# E17-PDU-POWER.net
KiCad netlist of a schematic drawn in Altium Designer
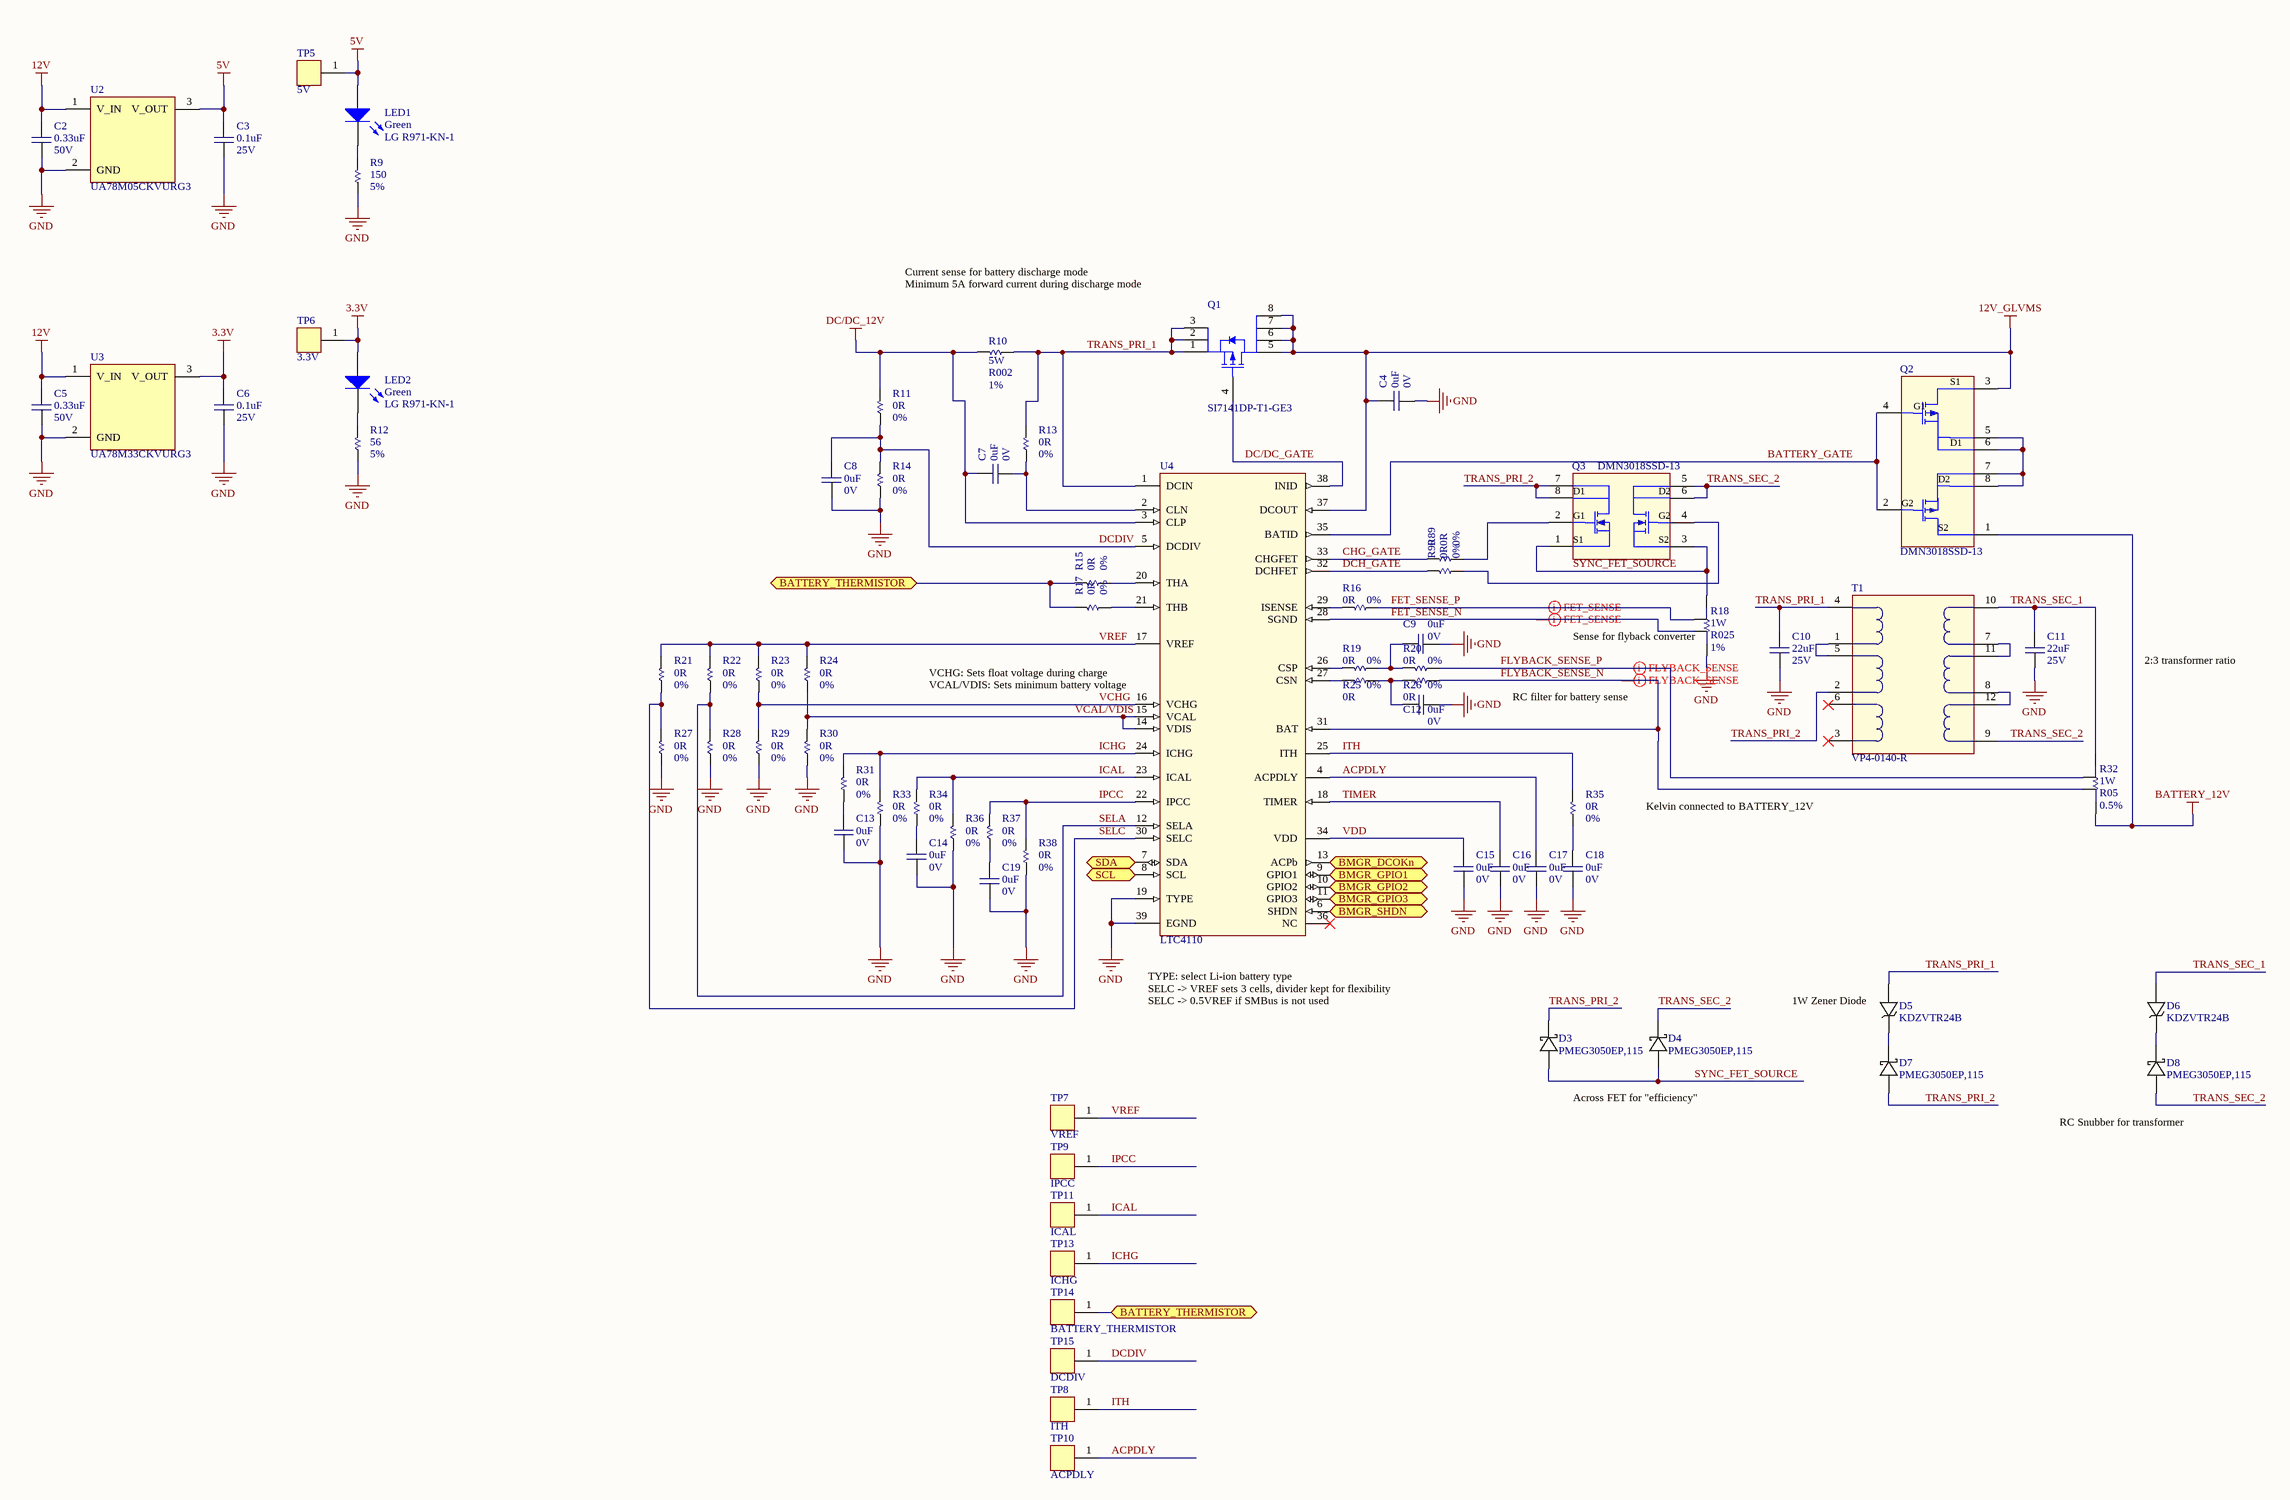
[diagram p0: E17-PDU-POWER.SchDoc]

(export (version "E")
  (design (tool "Eeschema 10.0.6"))
  (components
    (comp (ref "C2")
      (value "0.33uF")
      (footprint "C0805")
      (description "Generic 0805 Capacitor")
      (fields
        (field (name "TOLERANCE") "10%")
        (field (name "VOLTAGE") "50V")
        (field (name "Comment") "C_0805_Generic")
      )
      (libsource (lib "Compiled_PDU") (part "C_0805_Generic"))
    )
    (comp (ref "C3")
      (value "0.1uF")
      (footprint "C0805")
      (description "Generic 0805 Capacitor")
      (fields
        (field (name "TOLERANCE") "10%")
        (field (name "VOLTAGE") "25V")
        (field (name "Comment") "C_0805_Generic")
      )
      (libsource (lib "Compiled_PDU") (part "C_0805_Generic"))
    )
    (comp (ref "C4")
      (value "0uF")
      (footprint "C0603")
      (description "Generic 0603 Capacitor")
      (fields
        (field (name "TOLERANCE") "0%")
        (field (name "VOLTAGE") "0V")
        (field (name "Comment") "C_0603_Generic_1")
      )
      (libsource (lib "Compiled_PDU") (part "C_0603_Generic_1"))
    )
    (comp (ref "C5")
      (value "0.33uF")
      (footprint "C0805")
      (description "Generic 0805 Capacitor")
      (fields
        (field (name "TOLERANCE") "10%")
        (field (name "VOLTAGE") "50V")
        (field (name "Comment") "C_0805_Generic")
      )
      (libsource (lib "Compiled_PDU") (part "C_0805_Generic"))
    )
    (comp (ref "C6")
      (value "0.1uF")
      (footprint "C0805")
      (description "Generic 0805 Capacitor")
      (fields
        (field (name "TOLERANCE") "10%")
        (field (name "VOLTAGE") "25V")
        (field (name "Comment") "C_0805_Generic")
      )
      (libsource (lib "Compiled_PDU") (part "C_0805_Generic"))
    )
    (comp (ref "C7")
      (value "0uF")
      (footprint "C0603")
      (description "Generic 0603 Capacitor")
      (fields
        (field (name "TOLERANCE") "0%")
        (field (name "VOLTAGE") "0V")
        (field (name "Comment") "C_0603_Generic_1")
      )
      (libsource (lib "Compiled_PDU") (part "C_0603_Generic_1"))
    )
    (comp (ref "C8")
      (value "0uF")
      (footprint "C0603")
      (description "Generic 0603 Capacitor")
      (fields
        (field (name "TOLERANCE") "0%")
        (field (name "VOLTAGE") "0V")
        (field (name "Comment") "C_0603_Generic_1")
      )
      (libsource (lib "Compiled_PDU") (part "C_0603_Generic_1"))
    )
    (comp (ref "C9")
      (value "0uF")
      (footprint "C0402")
      (description "Generic 0402 Capacitor")
      (fields
        (field (name "TOLERANCE") "0%")
        (field (name "VOLTAGE") "0V")
        (field (name "Comment") "C_0403_Generic")
      )
      (libsource (lib "Compiled_PDU") (part "C_0403_Generic"))
    )
    (comp (ref "C10")
      (value "22uF")
      (footprint "C0805")
      (description "Generic 0805 Capacitor")
      (fields
        (field (name "TOLERANCE") "20%")
        (field (name "VOLTAGE") "25V")
        (field (name "Comment") "C_0805_Generic")
      )
      (libsource (lib "Compiled_PDU") (part "C_0805_Generic"))
    )
    (comp (ref "C11")
      (value "22uF")
      (footprint "C0805")
      (description "Generic 0805 Capacitor")
      (fields
        (field (name "TOLERANCE") "20%")
        (field (name "VOLTAGE") "25V")
        (field (name "Comment") "C_0805_Generic")
      )
      (libsource (lib "Compiled_PDU") (part "C_0805_Generic"))
    )
    (comp (ref "C12")
      (value "0uF")
      (footprint "C0402")
      (description "Generic 0402 Capacitor")
      (fields
        (field (name "TOLERANCE") "0%")
        (field (name "VOLTAGE") "0V")
        (field (name "Comment") "C_0403_Generic")
      )
      (libsource (lib "Compiled_PDU") (part "C_0403_Generic"))
    )
    (comp (ref "C13")
      (value "0uF")
      (footprint "C0402")
      (description "Generic 0402 Capacitor")
      (fields
        (field (name "TOLERANCE") "0%")
        (field (name "VOLTAGE") "0V")
        (field (name "Comment") "C_0403_Generic")
      )
      (libsource (lib "Compiled_PDU") (part "C_0403_Generic"))
    )
    (comp (ref "C14")
      (value "0uF")
      (footprint "C0402")
      (description "Generic 0402 Capacitor")
      (fields
        (field (name "TOLERANCE") "0%")
        (field (name "VOLTAGE") "0V")
        (field (name "Comment") "C_0403_Generic")
      )
      (libsource (lib "Compiled_PDU") (part "C_0403_Generic"))
    )
    (comp (ref "C15")
      (value "0uF")
      (footprint "C0603")
      (description "Generic 0603 Capacitor")
      (fields
        (field (name "TOLERANCE") "0%")
        (field (name "VOLTAGE") "0V")
        (field (name "Comment") "C_0603_Generic_1")
      )
      (libsource (lib "Compiled_PDU") (part "C_0603_Generic_1"))
    )
    (comp (ref "C16")
      (value "0uF")
      (footprint "C0402")
      (description "Generic 0402 Capacitor")
      (fields
        (field (name "TOLERANCE") "0%")
        (field (name "VOLTAGE") "0V")
        (field (name "Comment") "C_0403_Generic")
      )
      (libsource (lib "Compiled_PDU") (part "C_0403_Generic"))
    )
    (comp (ref "C17")
      (value "0uF")
      (footprint "C0402")
      (description "Generic 0402 Capacitor")
      (fields
        (field (name "TOLERANCE") "0%")
        (field (name "VOLTAGE") "0V")
        (field (name "Comment") "C_0403_Generic")
      )
      (libsource (lib "Compiled_PDU") (part "C_0403_Generic"))
    )
    (comp (ref "C18")
      (value "0uF")
      (footprint "C0402")
      (description "Generic 0402 Capacitor")
      (fields
        (field (name "TOLERANCE") "0%")
        (field (name "VOLTAGE") "0V")
        (field (name "Comment") "C_0403_Generic")
      )
      (libsource (lib "Compiled_PDU") (part "C_0403_Generic"))
    )
    (comp (ref "C19")
      (value "0uF")
      (footprint "C0402")
      (description "Generic 0402 Capacitor")
      (fields
        (field (name "TOLERANCE") "0%")
        (field (name "VOLTAGE") "0V")
        (field (name "Comment") "C_0403_Generic")
      )
      (libsource (lib "Compiled_PDU") (part "C_0403_Generic"))
    )
    (comp (ref "D3")
      (value "D_PMEG3050EP,115")
      (footprint "SOD-128")
      (description "DIODE SCHOTTKY 360mV 30V 5A")
      (fields (field (name "MFG") "Nexperia") (field (name "MFG_PN") "PMEG3050EP,115"))
      (libsource (lib "Compiled_PDU") (part "D_PMEG3050EP,115"))
    )
    (comp (ref "D4")
      (value "D_PMEG3050EP,115")
      (footprint "SOD-128")
      (description "DIODE SCHOTTKY 360mV 30V 5A")
      (fields (field (name "MFG") "Nexperia") (field (name "MFG_PN") "PMEG3050EP,115"))
      (libsource (lib "Compiled_PDU") (part "D_PMEG3050EP,115"))
    )
    (comp (ref "D5")
      (value "D_ZENER")
      (footprint "Compiled_PDU:SOD-123FL")
      (description "DIODE ZENER 24V 1W PMDU")
      (fields (field (name "MFG") "Rohm Semiconductor") (field (name "MFG_PN") "KDZVTR24B"))
      (libsource (lib "Compiled_PDU") (part "D_ZENER"))
    )
    (comp (ref "D6")
      (value "D_ZENER")
      (footprint "Compiled_PDU:SOD-123FL")
      (description "DIODE ZENER 24V 1W PMDU")
      (fields (field (name "MFG") "Rohm Semiconductor") (field (name "MFG_PN") "KDZVTR24B"))
      (libsource (lib "Compiled_PDU") (part "D_ZENER"))
    )
    (comp (ref "D7")
      (value "D_PMEG3050EP,115")
      (footprint "SOD-128")
      (description "DIODE SCHOTTKY 360mV 30V 5A")
      (fields (field (name "MFG") "Nexperia") (field (name "MFG_PN") "PMEG3050EP,115"))
      (libsource (lib "Compiled_PDU") (part "D_PMEG3050EP,115"))
    )
    (comp (ref "D8")
      (value "D_PMEG3050EP,115")
      (footprint "SOD-128")
      (description "DIODE SCHOTTKY 360mV 30V 5A")
      (fields (field (name "MFG") "Nexperia") (field (name "MFG_PN") "PMEG3050EP,115"))
      (libsource (lib "Compiled_PDU") (part "D_PMEG3050EP,115"))
    )
    (comp (ref "LED1")
      (value "Green")
      (footprint "LGR971")
      (description "Green LED")
      (fields (field (name "MFG") "OSRAM Opto Semiconductors Inc.") (field (name "MFG_PN") "LG R971-KN-1"))
      (libsource (lib "Compiled_PDU") (part "LED_LGR971"))
    )
    (comp (ref "LED2")
      (value "Green")
      (footprint "LGR971")
      (description "Green LED")
      (fields (field (name "MFG") "OSRAM Opto Semiconductors Inc.") (field (name "MFG_PN") "LG R971-KN-1"))
      (libsource (lib "Compiled_PDU") (part "LED_LGR971"))
    )
    (comp (ref "Q1")
      (value "Q_SI7141DP-T1-GE3")
      (footprint "PowerPak SO-8")
      (description "P-CH 20V 60A PowerPak SO-8")
      (fields (field (name "MFG") "Vishay") (field (name "MFG_PN") "SI7141DP-T1-GE3"))
      (libsource (lib "Compiled_PDU") (part "Q_SI7141DP-T1-GE3"))
    )
    (comp (ref "Q2")
      (value "Q_DMN3018SSD-13_1")
      (footprint "8-SOIC")
      (description "2x P-ch FET 40V 6.7A")
      (fields (field (name "MFG") "ON Semiconductor") (field (name "MFG_PN") "DMN3018SSD-13"))
      (libsource (lib "Compiled_PDU") (part "Q_DMN3018SSD-13_1"))
    )
    (comp (ref "Q3")
      (value "Q_DMN3018SSD-13")
      (footprint "8-SOIC")
      (description "2x N-ch FET 40V 6.7A")
      (fields (field (name "MFG") "ON Semiconductor") (field (name "MFG_PN") "DMN3018SSD-13"))
      (libsource (lib "Compiled_PDU") (part "Q_DMN3018SSD-13"))
    )
    (comp (ref "R9")
      (value "150")
      (footprint "R0805")
      (description "Generic 0805 Resistor")
      (fields
        (field (name "POWER") "1/8W")
        (field (name "TOLERANCE") "5%")
        (field (name "Comment") "R_0805_Generic")
      )
      (libsource (lib "Compiled_PDU") (part "R_0805_Generic"))
    )
    (comp (ref "R10")
      (value "R002")
      (footprint "R2526")
      (description "RES CURRENT SENSE R002 1% 5W")
      (fields
        (field (name "MFG") "Panasonic")
        (field (name "POWER") "5W")
        (field (name "TOLERANCE") "1%")
        (field (name "Comment") "R_ERJ-MS6SF2M0U")
      )
      (libsource (lib "Compiled_PDU") (part "R_ERJ-MS6SF2M0U"))
    )
    (comp (ref "R11")
      (value "0R")
      (footprint "R0603")
      (description "Generic 0603 Resistor")
      (fields
        (field (name "POWER") "0W")
        (field (name "TOLERANCE") "0%")
        (field (name "Comment") "R_0603_Generic")
      )
      (libsource (lib "Compiled_PDU") (part "R_0603_Generic"))
    )
    (comp (ref "R12")
      (value "56")
      (footprint "R0805")
      (description "Generic 0805 Resistor")
      (fields
        (field (name "POWER") "1/8W")
        (field (name "TOLERANCE") "5%")
        (field (name "Comment") "R_0805_Generic")
      )
      (libsource (lib "Compiled_PDU") (part "R_0805_Generic"))
    )
    (comp (ref "R13")
      (value "0R")
      (footprint "R0603")
      (description "Generic 0603 Resistor")
      (fields
        (field (name "POWER") "0W")
        (field (name "TOLERANCE") "0%")
        (field (name "Comment") "R_0603_Generic")
      )
      (libsource (lib "Compiled_PDU") (part "R_0603_Generic"))
    )
    (comp (ref "R14")
      (value "0R")
      (footprint "R0603")
      (description "Generic 0603 Resistor")
      (fields
        (field (name "POWER") "0W")
        (field (name "TOLERANCE") "0%")
        (field (name "Comment") "R_0603_Generic")
      )
      (libsource (lib "Compiled_PDU") (part "R_0603_Generic"))
    )
    (comp (ref "R15")
      (value "0R")
      (footprint "R0603")
      (description "Generic 0603 Resistor")
      (fields
        (field (name "POWER") "0W")
        (field (name "TOLERANCE") "0%")
        (field (name "Comment") "R_0603_Generic")
      )
      (libsource (lib "Compiled_PDU") (part "R_0603_Generic"))
    )
    (comp (ref "R16")
      (value "0R")
      (footprint "R0402")
      (description "Generic 0402 Resistor")
      (fields
        (field (name "POWER") "0W")
        (field (name "TOLERANCE") "0%")
        (field (name "Comment") "R_0402_Generic")
      )
      (libsource (lib "Compiled_PDU") (part "R_0402_Generic"))
    )
    (comp (ref "R17")
      (value "0R")
      (footprint "R0603")
      (description "Generic 0603 Resistor")
      (fields
        (field (name "POWER") "0W")
        (field (name "TOLERANCE") "0%")
        (field (name "Comment") "R_0603_Generic")
      )
      (libsource (lib "Compiled_PDU") (part "R_0603_Generic"))
    )
    (comp (ref "R18")
      (value "R025")
      (footprint "R2512")
      (description "RES CURRENT SENSE R025 1% 1W")
      (fields
        (field (name "MFG") "Ohmite")
        (field (name "POWER") "1W")
        (field (name "TOLERANCE") "1%")
        (field (name "Comment") "R_LVK24R025FER")
      )
      (libsource (lib "Compiled_PDU") (part "R_LVK24R025FER"))
    )
    (comp (ref "R19")
      (value "0R")
      (footprint "R0402")
      (description "Generic 0402 Resistor")
      (fields
        (field (name "POWER") "0W")
        (field (name "TOLERANCE") "0%")
        (field (name "Comment") "R_0402_Generic")
      )
      (libsource (lib "Compiled_PDU") (part "R_0402_Generic"))
    )
    (comp (ref "R20")
      (value "0R")
      (footprint "R0402")
      (description "Generic 0402 Resistor")
      (fields
        (field (name "POWER") "0W")
        (field (name "TOLERANCE") "0%")
        (field (name "Comment") "R_0402_Generic")
      )
      (libsource (lib "Compiled_PDU") (part "R_0402_Generic"))
    )
    (comp (ref "R21")
      (value "0R")
      (footprint "R0402")
      (description "Generic 0402 Resistor")
      (fields
        (field (name "POWER") "0W")
        (field (name "TOLERANCE") "0%")
        (field (name "Comment") "R_0402_Generic")
      )
      (libsource (lib "Compiled_PDU") (part "R_0402_Generic"))
    )
    (comp (ref "R22")
      (value "0R")
      (footprint "R0402")
      (description "Generic 0402 Resistor")
      (fields
        (field (name "POWER") "0W")
        (field (name "TOLERANCE") "0%")
        (field (name "Comment") "R_0402_Generic")
      )
      (libsource (lib "Compiled_PDU") (part "R_0402_Generic"))
    )
    (comp (ref "R23")
      (value "0R")
      (footprint "R0402")
      (description "Generic 0402 Resistor")
      (fields
        (field (name "POWER") "0W")
        (field (name "TOLERANCE") "0%")
        (field (name "Comment") "R_0402_Generic")
      )
      (libsource (lib "Compiled_PDU") (part "R_0402_Generic"))
    )
    (comp (ref "R24")
      (value "0R")
      (footprint "R0402")
      (description "Generic 0402 Resistor")
      (fields
        (field (name "POWER") "0W")
        (field (name "TOLERANCE") "0%")
        (field (name "Comment") "R_0402_Generic")
      )
      (libsource (lib "Compiled_PDU") (part "R_0402_Generic"))
    )
    (comp (ref "R25")
      (value "0R")
      (footprint "R0402")
      (description "Generic 0402 Resistor")
      (fields
        (field (name "POWER") "0W")
        (field (name "TOLERANCE") "0%")
        (field (name "Comment") "R_0402_Generic")
      )
      (libsource (lib "Compiled_PDU") (part "R_0402_Generic"))
    )
    (comp (ref "R26")
      (value "0R")
      (footprint "R0402")
      (description "Generic 0402 Resistor")
      (fields
        (field (name "POWER") "0W")
        (field (name "TOLERANCE") "0%")
        (field (name "Comment") "R_0402_Generic")
      )
      (libsource (lib "Compiled_PDU") (part "R_0402_Generic"))
    )
    (comp (ref "R27")
      (value "0R")
      (footprint "R0402")
      (description "Generic 0402 Resistor")
      (fields
        (field (name "POWER") "0W")
        (field (name "TOLERANCE") "0%")
        (field (name "Comment") "R_0402_Generic")
      )
      (libsource (lib "Compiled_PDU") (part "R_0402_Generic"))
    )
    (comp (ref "R28")
      (value "0R")
      (footprint "R0402")
      (description "Generic 0402 Resistor")
      (fields
        (field (name "POWER") "0W")
        (field (name "TOLERANCE") "0%")
        (field (name "Comment") "R_0402_Generic")
      )
      (libsource (lib "Compiled_PDU") (part "R_0402_Generic"))
    )
    (comp (ref "R29")
      (value "0R")
      (footprint "R0402")
      (description "Generic 0402 Resistor")
      (fields
        (field (name "POWER") "0W")
        (field (name "TOLERANCE") "0%")
        (field (name "Comment") "R_0402_Generic")
      )
      (libsource (lib "Compiled_PDU") (part "R_0402_Generic"))
    )
    (comp (ref "R30")
      (value "0R")
      (footprint "R0402")
      (description "Generic 0402 Resistor")
      (fields
        (field (name "POWER") "0W")
        (field (name "TOLERANCE") "0%")
        (field (name "Comment") "R_0402_Generic")
      )
      (libsource (lib "Compiled_PDU") (part "R_0402_Generic"))
    )
    (comp (ref "R31")
      (value "0R")
      (footprint "R0402")
      (description "Generic 0402 Resistor")
      (fields
        (field (name "POWER") "0W")
        (field (name "TOLERANCE") "0%")
        (field (name "Comment") "R_0402_Generic")
      )
      (libsource (lib "Compiled_PDU") (part "R_0402_Generic"))
    )
    (comp (ref "R32")
      (value "R05")
      (footprint "R2512")
      (description "RES CURRENT SENSE R05 0.5% 1W")
      (fields
        (field (name "MFG") "Ohmite")
        (field (name "POWER") "1W")
        (field (name "TOLERANCE") "0.5%")
        (field (name "Comment") "R_LVK24R050DER")
      )
      (libsource (lib "Compiled_PDU") (part "R_LVK24R050DER"))
    )
    (comp (ref "R33")
      (value "0R")
      (footprint "R0402")
      (description "Generic 0402 Resistor")
      (fields
        (field (name "POWER") "0W")
        (field (name "TOLERANCE") "0%")
        (field (name "Comment") "R_0402_Generic")
      )
      (libsource (lib "Compiled_PDU") (part "R_0402_Generic"))
    )
    (comp (ref "R34")
      (value "0R")
      (footprint "R0402")
      (description "Generic 0402 Resistor")
      (fields
        (field (name "POWER") "0W")
        (field (name "TOLERANCE") "0%")
        (field (name "Comment") "R_0402_Generic")
      )
      (libsource (lib "Compiled_PDU") (part "R_0402_Generic"))
    )
    (comp (ref "R35")
      (value "0R")
      (footprint "R0402")
      (description "Generic 0402 Resistor")
      (fields
        (field (name "POWER") "0W")
        (field (name "TOLERANCE") "0%")
        (field (name "Comment") "R_0402_Generic")
      )
      (libsource (lib "Compiled_PDU") (part "R_0402_Generic"))
    )
    (comp (ref "R36")
      (value "0R")
      (footprint "R0402")
      (description "Generic 0402 Resistor")
      (fields
        (field (name "POWER") "0W")
        (field (name "TOLERANCE") "0%")
        (field (name "Comment") "R_0402_Generic")
      )
      (libsource (lib "Compiled_PDU") (part "R_0402_Generic"))
    )
    (comp (ref "R37")
      (value "0R")
      (footprint "R0402")
      (description "Generic 0402 Resistor")
      (fields
        (field (name "POWER") "0W")
        (field (name "TOLERANCE") "0%")
        (field (name "Comment") "R_0402_Generic")
      )
      (libsource (lib "Compiled_PDU") (part "R_0402_Generic"))
    )
    (comp (ref "R38")
      (value "0R")
      (footprint "R0402")
      (description "Generic 0402 Resistor")
      (fields
        (field (name "POWER") "0W")
        (field (name "TOLERANCE") "0%")
        (field (name "Comment") "R_0402_Generic")
      )
      (libsource (lib "Compiled_PDU") (part "R_0402_Generic"))
    )
    (comp (ref "R89")
      (value "0R")
      (footprint "R0603")
      (description "Generic 0603 Resistor")
      (fields
        (field (name "POWER") "0W")
        (field (name "TOLERANCE") "0%")
        (field (name "Comment") "R_0603_Generic")
      )
      (libsource (lib "Compiled_PDU") (part "R_0603_Generic"))
    )
    (comp (ref "R90")
      (value "0R")
      (footprint "R0603")
      (description "Generic 0603 Resistor")
      (fields
        (field (name "POWER") "0W")
        (field (name "TOLERANCE") "0%")
        (field (name "Comment") "R_0603_Generic")
      )
      (libsource (lib "Compiled_PDU") (part "R_0603_Generic"))
    )
    (comp (ref "T1")
      (value "T_VP4-0140-R")
      (footprint "T_VP4-0140-R")
      (description "Transformer 6 coil 11.3uH")
      (fields (field (name "MFG") "Eaton") (field (name "MFG_PN") "VP4-0140-R"))
      (libsource (lib "Compiled_PDU") (part "T_VP4-0140-R"))
    )
    (comp (ref "TP5")
      (value "5V")
      (footprint "TEST POINT")
      (description "Test Point")
      (libsource (lib "Compiled_PDU") (part "Test Point"))
    )
    (comp (ref "TP6")
      (value "3.3V")
      (footprint "TEST POINT")
      (description "Test Point")
      (libsource (lib "Compiled_PDU") (part "Test Point"))
    )
    (comp (ref "TP7")
      (value "VREF")
      (footprint "TEST POINT")
      (description "Test Point")
      (libsource (lib "Compiled_PDU") (part "Test Point"))
    )
    (comp (ref "TP8")
      (value "ITH")
      (footprint "TEST POINT")
      (description "Test Point")
      (libsource (lib "Compiled_PDU") (part "Test Point"))
    )
    (comp (ref "TP9")
      (value "IPCC")
      (footprint "TEST POINT")
      (description "Test Point")
      (libsource (lib "Compiled_PDU") (part "Test Point"))
    )
    (comp (ref "TP10")
      (value "ACPDLY")
      (footprint "TEST POINT")
      (description "Test Point")
      (libsource (lib "Compiled_PDU") (part "Test Point"))
    )
    (comp (ref "TP11")
      (value "ICAL")
      (footprint "TEST POINT")
      (description "Test Point")
      (libsource (lib "Compiled_PDU") (part "Test Point"))
    )
    (comp (ref "TP13")
      (value "ICHG")
      (footprint "TEST POINT")
      (description "Test Point")
      (libsource (lib "Compiled_PDU") (part "Test Point"))
    )
    (comp (ref "TP14")
      (value "BATTERY_THERMISTOR")
      (footprint "TEST POINT")
      (description "Test Point")
      (libsource (lib "Compiled_PDU") (part "Test Point"))
    )
    (comp (ref "TP15")
      (value "DCDIV")
      (footprint "TEST POINT")
      (description "Test Point")
      (libsource (lib "Compiled_PDU") (part "Test Point"))
    )
    (comp (ref "U2")
      (value "U_UA78M05CKVURG3")
      (footprint "TO-252-3")
      (description "5V 500mA Linear Regulator")
      (fields (field (name "MFG") "TI") (field (name "MFG_PN") "UA78M05CKVURG3"))
      (libsource (lib "Compiled_PDU") (part "U_UA78M05CKVURG3"))
    )
    (comp (ref "U3")
      (value "U_UA78M33CKVURG3")
      (footprint "TO-252-3")
      (description "3.3V 500mA Linear Regulator")
      (fields (field (name "MFG") "TI") (field (name "MFG_PN") "UA78M33CKVURG3"))
      (libsource (lib "Compiled_PDU") (part "U_UA78M33CKVURG3"))
    )
    (comp (ref "U4")
      (value "U_LTC4110")
      (footprint "U_LTC4110")
      (description "IC Battery Backup Manager")
      (fields (field (name "MFG") "Linear Technology") (field (name "MFG_PN") "LTC4110"))
      (libsource (lib "Compiled_PDU") (part "U_LTC4110"))
    )
  )
  (nets
    (net (code "1") (name "/ACPDLY") (class "Default")
      (node (ref "C17") (pin "1") (pinfunction "EGND_1") (pintype "passive"))
      (node (ref "TP10") (pin "1") (pintype "passive"))
      (node (ref "U4") (pin "4") (pinfunction "ACPDLY_4") (pintype "passive"))
    )
    (net (code "2") (name "/BATTERY_GATE") (class "Default")
      (node (ref "Q2") (pin "2") (pintype "passive"))
      (node (ref "Q2") (pin "4") (pinfunction "4_4") (pintype "passive"))
      (node (ref "U4") (pin "35") (pinfunction "BATID_35") (pintype "output"))
    )
    (net (code "3") (name "/BATTERY_THERMISTOR") (class "Default")
      (node (ref "R15") (pin "1") (pinfunction "1_1") (pintype "passive"))
      (node (ref "R17") (pin "1") (pinfunction "1_1") (pintype "passive"))
      (node (ref "TP14") (pin "1") (pintype "passive"))
    )
    (net (code "4") (name "/BMGR_DCOKn") (class "Default")
      (node (ref "U4") (pin "13") (pinfunction "ACPb_13") (pintype "output"))
    )
    (net (code "5") (name "/BMGR_GPIO1") (class "Default")
      (node (ref "U4") (pin "9") (pinfunction "GPIO1_9") (pintype "bidirectional"))
    )
    (net (code "6") (name "/BMGR_GPIO2") (class "Default")
      (node (ref "U4") (pin "10") (pinfunction "GPIO2_10") (pintype "bidirectional"))
    )
    (net (code "7") (name "/BMGR_GPIO3") (class "Default")
      (node (ref "U4") (pin "11") (pinfunction "GPIO3_11") (pintype "bidirectional"))
    )
    (net (code "8") (name "/BMGR_SHDN") (class "Default")
      (node (ref "U4") (pin "6") (pinfunction "SHDN_6") (pintype "input"))
    )
    (net (code "9") (name "/CHG_GATE") (class "Default")
      (node (ref "R89") (pin "1") (pinfunction "1_1") (pintype "passive"))
      (node (ref "U4") (pin "33") (pinfunction "CHGFET_33") (pintype "output"))
    )
    (net (code "10") (name "/DCDIV") (class "Default")
      (node (ref "C8") (pin "1") (pinfunction "EGND_1") (pintype "passive"))
      (node (ref "R11") (pin "2") (pinfunction "2_2") (pintype "passive"))
      (node (ref "R14") (pin "1") (pinfunction "1_1") (pintype "passive"))
      (node (ref "TP15") (pin "1") (pintype "passive"))
      (node (ref "U4") (pin "5") (pinfunction "DCDIV_5") (pintype "input"))
    )
    (net (code "11") (name "/DCH_GATE") (class "Default")
      (node (ref "R90") (pin "1") (pinfunction "1_1") (pintype "passive"))
      (node (ref "U4") (pin "32") (pinfunction "DCHFET_32") (pintype "output"))
    )
    (net (code "12") (name "/DC{slash}DC_GATE") (class "Default")
      (node (ref "Q1") (pin "4") (pinfunction "G_4") (pintype "passive"))
      (node (ref "U4") (pin "38") (pinfunction "INID_38") (pintype "output"))
    )
    (net (code "13") (name "/FET_SENSE_N") (class "Default")
      (node (ref "R18") (pin "3") (pinfunction "3_3") (pintype "passive"))
      (node (ref "U4") (pin "28") (pinfunction "SGND_28") (pintype "input"))
    )
    (net (code "14") (name "/FET_SENSE_P") (class "Default")
      (node (ref "R16") (pin "2") (pinfunction "2_2") (pintype "passive"))
      (node (ref "R18") (pin "4") (pinfunction "4_4") (pintype "passive"))
    )
    (net (code "15") (name "/FLYBACK_SENSE_N") (class "Default")
      (node (ref "R26") (pin "2") (pinfunction "2_2") (pintype "passive"))
      (node (ref "R32") (pin "3") (pinfunction "3_3") (pintype "passive"))
      (node (ref "U4") (pin "31") (pinfunction "BAT_31") (pintype "input"))
    )
    (net (code "16") (name "/FLYBACK_SENSE_P") (class "Default")
      (node (ref "R20") (pin "2") (pinfunction "2_2") (pintype "passive"))
      (node (ref "R32") (pin "4") (pinfunction "4_4") (pintype "passive"))
    )
    (net (code "17") (name "/ICAL") (class "Default")
      (node (ref "R34") (pin "1") (pinfunction "1_1") (pintype "passive"))
      (node (ref "R36") (pin "1") (pinfunction "1_1") (pintype "passive"))
      (node (ref "TP11") (pin "1") (pintype "passive"))
      (node (ref "U4") (pin "23") (pinfunction "ICAL_23") (pintype "input"))
    )
    (net (code "18") (name "/ICHG") (class "Default")
      (node (ref "R31") (pin "1") (pinfunction "1_1") (pintype "passive"))
      (node (ref "R33") (pin "1") (pinfunction "1_1") (pintype "passive"))
      (node (ref "TP13") (pin "1") (pintype "passive"))
      (node (ref "U4") (pin "24") (pinfunction "ICHG_24") (pintype "input"))
    )
    (net (code "19") (name "/IPCC") (class "Default")
      (node (ref "R37") (pin "1") (pinfunction "1_1") (pintype "passive"))
      (node (ref "R38") (pin "1") (pinfunction "1_1") (pintype "passive"))
      (node (ref "TP9") (pin "1") (pintype "passive"))
      (node (ref "U4") (pin "22") (pinfunction "IPCC_22") (pintype "input"))
    )
    (net (code "20") (name "/ITH") (class "Default")
      (node (ref "R35") (pin "1") (pinfunction "1_1") (pintype "passive"))
      (node (ref "TP8") (pin "1") (pintype "passive"))
      (node (ref "U4") (pin "25") (pinfunction "ITH_25") (pintype "passive"))
    )
    (net (code "21") (name "/SCL") (class "Default")
      (node (ref "U4") (pin "8") (pinfunction "SCL_8") (pintype "input"))
    )
    (net (code "22") (name "/SDA") (class "Default")
      (node (ref "U4") (pin "7") (pinfunction "SDA_7") (pintype "bidirectional"))
    )
    (net (code "23") (name "/SELA") (class "Default")
      (node (ref "R22") (pin "2") (pinfunction "2_2") (pintype "passive"))
      (node (ref "R28") (pin "1") (pinfunction "1_1") (pintype "passive"))
      (node (ref "U4") (pin "12") (pinfunction "SELA_12") (pintype "input"))
    )
    (net (code "24") (name "/SELC") (class "Default")
      (node (ref "R21") (pin "2") (pinfunction "2_2") (pintype "passive"))
      (node (ref "R27") (pin "1") (pinfunction "1_1") (pintype "passive"))
      (node (ref "U4") (pin "30") (pinfunction "SELC_30") (pintype "input"))
    )
    (net (code "25") (name "/SYNC_FET_SOURCE") (class "Default")
      (node (ref "D3") (pin "1") (pintype "passive"))
      (node (ref "D4") (pin "1") (pintype "passive"))
      (node (ref "Q3") (pin "1") (pintype "passive"))
      (node (ref "Q3") (pin "3") (pinfunction "3_3") (pintype "passive"))
      (node (ref "R18") (pin "2") (pinfunction "2_2") (pintype "passive"))
    )
    (net (code "26") (name "/TIMER") (class "Default")
      (node (ref "C16") (pin "1") (pinfunction "EGND_1") (pintype "passive"))
      (node (ref "U4") (pin "18") (pinfunction "TIMER_18") (pintype "input"))
    )
    (net (code "27") (name "/TRANS_PRI_1") (class "Default")
      (node (ref "C10") (pin "1") (pinfunction "EGND_1") (pintype "passive"))
      (node (ref "D5") (pin "1") (pintype "passive"))
      (node (ref "Q1") (pin "1") (pintype "passive"))
      (node (ref "Q1") (pin "2") (pinfunction "5_2") (pintype "passive"))
      (node (ref "Q1") (pin "3") (pinfunction "6_3") (pintype "passive"))
      (node (ref "R10") (pin "2") (pinfunction "2_2") (pintype "passive"))
      (node (ref "R13") (pin "1") (pinfunction "1_1") (pintype "passive"))
      (node (ref "T1") (pin "4") (pinfunction "4_4") (pintype "passive"))
      (node (ref "U4") (pin "1") (pinfunction "DCIN_1") (pintype "power_in"))
    )
    (net (code "28") (name "/TRANS_PRI_2") (class "Default")
      (node (ref "D3") (pin "2") (pintype "passive"))
      (node (ref "D7") (pin "1") (pintype "passive"))
      (node (ref "Q3") (pin "7") (pinfunction "7_7") (pintype "passive"))
      (node (ref "Q3") (pin "8") (pinfunction "8_8") (pintype "passive"))
      (node (ref "T1") (pin "2") (pinfunction "2_2") (pintype "passive"))
    )
    (net (code "29") (name "/TRANS_SEC_1") (class "Default")
      (node (ref "C11") (pin "1") (pinfunction "EGND_1") (pintype "passive"))
      (node (ref "D6") (pin "1") (pintype "passive"))
      (node (ref "R32") (pin "2") (pinfunction "2_2") (pintype "passive"))
      (node (ref "T1") (pin "10") (pinfunction "10_10") (pintype "passive"))
    )
    (net (code "30") (name "/TRANS_SEC_2") (class "Default")
      (node (ref "D4") (pin "2") (pintype "passive"))
      (node (ref "D8") (pin "1") (pintype "passive"))
      (node (ref "Q3") (pin "5") (pinfunction "5_5") (pintype "passive"))
      (node (ref "Q3") (pin "6") (pinfunction "6_6") (pintype "passive"))
      (node (ref "T1") (pin "9") (pinfunction "9_9") (pintype "passive"))
    )
    (net (code "31") (name "/VCAL{slash}VDIS") (class "Default")
      (node (ref "R24") (pin "2") (pinfunction "2_2") (pintype "passive"))
      (node (ref "R30") (pin "1") (pinfunction "1_1") (pintype "passive"))
      (node (ref "U4") (pin "14") (pinfunction "VDIS_14") (pintype "input"))
      (node (ref "U4") (pin "15") (pinfunction "VCAL_15") (pintype "input"))
    )
    (net (code "32") (name "/VCHG") (class "Default")
      (node (ref "R23") (pin "2") (pinfunction "2_2") (pintype "passive"))
      (node (ref "R29") (pin "1") (pinfunction "1_1") (pintype "passive"))
      (node (ref "U4") (pin "16") (pinfunction "VCHG_16") (pintype "input"))
    )
    (net (code "33") (name "/VDD") (class "Default")
      (node (ref "C15") (pin "1") (pinfunction "EGND_1") (pintype "passive"))
      (node (ref "U4") (pin "34") (pinfunction "VDD_34") (pintype "power_in"))
    )
    (net (code "34") (name "/VREF") (class "Default")
      (node (ref "R21") (pin "1") (pinfunction "1_1") (pintype "passive"))
      (node (ref "R22") (pin "1") (pinfunction "1_1") (pintype "passive"))
      (node (ref "R23") (pin "1") (pinfunction "1_1") (pintype "passive"))
      (node (ref "R24") (pin "1") (pinfunction "1_1") (pintype "passive"))
      (node (ref "TP7") (pin "1") (pintype "passive"))
      (node (ref "U4") (pin "17") (pinfunction "VREF_17") (pintype "power_in"))
    )
    (net (code "35") (name "3.3V") (class "Default")
      (node (ref "C6") (pin "1") (pinfunction "EGND_1") (pintype "passive"))
      (node (ref "LED2") (pin "1") (pinfunction "A_1") (pintype "passive"))
      (node (ref "TP6") (pin "1") (pintype "passive"))
      (node (ref "U3") (pin "3") (pinfunction "V_OUT_3") (pintype "power_in"))
    )
    (net (code "36") (name "5V") (class "Default")
      (node (ref "C3") (pin "1") (pinfunction "EGND_1") (pintype "passive"))
      (node (ref "LED1") (pin "1") (pinfunction "A_1") (pintype "passive"))
      (node (ref "TP5") (pin "1") (pintype "passive"))
      (node (ref "U2") (pin "3") (pinfunction "V_OUT_3") (pintype "power_in"))
    )
    (net (code "37") (name "12V") (class "Default")
      (node (ref "C2") (pin "1") (pinfunction "EGND_1") (pintype "passive"))
      (node (ref "C5") (pin "1") (pinfunction "EGND_1") (pintype "passive"))
      (node (ref "U2") (pin "1") (pinfunction "V_IN_1") (pintype "power_in"))
      (node (ref "U3") (pin "1") (pinfunction "V_IN_1") (pintype "passive"))
    )
    (net (code "38") (name "12V_GLVMS") (class "Default")
      (node (ref "C4") (pin "1") (pinfunction "EGND_1") (pintype "passive"))
      (node (ref "Q1") (pin "5") (pinfunction "5_5") (pintype "passive"))
      (node (ref "Q1") (pin "6") (pinfunction "6_6") (pintype "passive"))
      (node (ref "Q1") (pin "7") (pinfunction "7_7") (pintype "passive"))
      (node (ref "Q1") (pin "8") (pinfunction "8_8") (pintype "passive"))
      (node (ref "Q2") (pin "3") (pinfunction "3_3") (pintype "passive"))
      (node (ref "U4") (pin "37") (pinfunction "DCOUT_37") (pintype "input"))
    )
    (net (code "39") (name "BATTERY_12V") (class "Default")
      (node (ref "Q2") (pin "1") (pintype "passive"))
      (node (ref "R32") (pin "1") (pinfunction "1_1") (pintype "passive"))
    )
    (net (code "40") (name "DC{slash}DC_12V") (class "Default")
      (node (ref "C7") (pin "1") (pinfunction "EGND_1") (pintype "passive"))
      (node (ref "R10") (pin "1") (pinfunction "1_1") (pintype "passive"))
      (node (ref "R11") (pin "1") (pinfunction "1_1") (pintype "passive"))
      (node (ref "U4") (pin "3") (pinfunction "CLP_3") (pintype "input"))
    )
    (net (code "41") (name "GND") (class "Default")
      (node (ref "C10") (pin "2") (pinfunction "2_2") (pintype "passive"))
      (node (ref "C11") (pin "2") (pinfunction "2_2") (pintype "passive"))
      (node (ref "C12") (pin "1") (pinfunction "EGND_1") (pintype "passive"))
      (node (ref "C13") (pin "2") (pinfunction "2_2") (pintype "passive"))
      (node (ref "C14") (pin "2") (pinfunction "2_2") (pintype "passive"))
      (node (ref "C15") (pin "2") (pinfunction "2_2") (pintype "passive"))
      (node (ref "C16") (pin "2") (pinfunction "2_2") (pintype "passive"))
      (node (ref "C17") (pin "2") (pinfunction "2_2") (pintype "passive"))
      (node (ref "C18") (pin "2") (pinfunction "2_2") (pintype "passive"))
      (node (ref "C19") (pin "2") (pinfunction "2_2") (pintype "passive"))
      (node (ref "C2") (pin "2") (pinfunction "2_2") (pintype "passive"))
      (node (ref "C3") (pin "2") (pinfunction "2_2") (pintype "passive"))
      (node (ref "C4") (pin "2") (pinfunction "2_2") (pintype "passive"))
      (node (ref "C5") (pin "2") (pinfunction "2_2") (pintype "passive"))
      (node (ref "C6") (pin "2") (pinfunction "2_2") (pintype "passive"))
      (node (ref "C8") (pin "2") (pinfunction "2_2") (pintype "passive"))
      (node (ref "C9") (pin "2") (pinfunction "2_2") (pintype "passive"))
      (node (ref "R12") (pin "2") (pinfunction "2_2") (pintype "passive"))
      (node (ref "R14") (pin "2") (pinfunction "2_2") (pintype "passive"))
      (node (ref "R18") (pin "1") (pinfunction "1_1") (pintype "passive"))
      (node (ref "R27") (pin "2") (pinfunction "2_2") (pintype "passive"))
      (node (ref "R28") (pin "2") (pinfunction "2_2") (pintype "passive"))
      (node (ref "R29") (pin "2") (pinfunction "2_2") (pintype "passive"))
      (node (ref "R30") (pin "2") (pinfunction "2_2") (pintype "passive"))
      (node (ref "R33") (pin "2") (pinfunction "2_2") (pintype "passive"))
      (node (ref "R36") (pin "2") (pinfunction "2_2") (pintype "passive"))
      (node (ref "R38") (pin "2") (pinfunction "2_2") (pintype "passive"))
      (node (ref "R9") (pin "2") (pinfunction "2_2") (pintype "passive"))
      (node (ref "U2") (pin "2") (pinfunction "GND_2") (pintype "power_in"))
      (node (ref "U3") (pin "2") (pinfunction "GND_2") (pintype "power_in"))
      (node (ref "U4") (pin "19") (pinfunction "TYPE_19") (pintype "input"))
      (node (ref "U4") (pin "39") (pinfunction "EGND_39") (pintype "power_in"))
    )
    (net (code "42") (name "Net-(C9-EGND)") (class "Default")
      (node (ref "C9") (pin "1") (pinfunction "EGND_1") (pintype "passive"))
      (node (ref "R19") (pin "2") (pinfunction "2_2") (pintype "passive"))
      (node (ref "R20") (pin "1") (pinfunction "1_1") (pintype "passive"))
    )
    (net (code "43") (name "Net-(C12-Pad2)") (class "Default")
      (node (ref "C12") (pin "2") (pinfunction "2_2") (pintype "passive"))
      (node (ref "R25") (pin "2") (pinfunction "2_2") (pintype "passive"))
      (node (ref "R26") (pin "1") (pinfunction "1_1") (pintype "passive"))
    )
    (net (code "44") (name "Net-(C13-EGND)") (class "Default")
      (node (ref "C13") (pin "1") (pinfunction "EGND_1") (pintype "passive"))
      (node (ref "R31") (pin "2") (pinfunction "2_2") (pintype "passive"))
    )
    (net (code "45") (name "Net-(C14-EGND)") (class "Default")
      (node (ref "C14") (pin "1") (pinfunction "EGND_1") (pintype "passive"))
      (node (ref "R34") (pin "2") (pinfunction "2_2") (pintype "passive"))
    )
    (net (code "46") (name "Net-(C18-EGND)") (class "Default")
      (node (ref "C18") (pin "1") (pinfunction "EGND_1") (pintype "passive"))
      (node (ref "R35") (pin "2") (pinfunction "2_2") (pintype "passive"))
    )
    (net (code "47") (name "Net-(C19-EGND)") (class "Default")
      (node (ref "C19") (pin "1") (pinfunction "EGND_1") (pintype "passive"))
      (node (ref "R37") (pin "2") (pinfunction "2_2") (pintype "passive"))
    )
    (net (code "48") (name "Net-(D5-Pad2)") (class "Default")
      (node (ref "D5") (pin "2") (pintype "passive"))
      (node (ref "D7") (pin "2") (pintype "passive"))
    )
    (net (code "49") (name "Net-(D6-Pad2)") (class "Default")
      (node (ref "D6") (pin "2") (pintype "passive"))
      (node (ref "D8") (pin "2") (pintype "passive"))
    )
    (net (code "50") (name "Net-(LED1-K)") (class "Default")
      (node (ref "LED1") (pin "2") (pinfunction "K_2") (pintype "passive"))
      (node (ref "R9") (pin "1") (pinfunction "1_1") (pintype "passive"))
    )
    (net (code "51") (name "Net-(LED2-K)") (class "Default")
      (node (ref "LED2") (pin "2") (pinfunction "K_2") (pintype "passive"))
      (node (ref "R12") (pin "1") (pinfunction "1_1") (pintype "passive"))
    )
    (net (code "52") (name "Net-(Q2-Pad5)") (class "Default")
      (node (ref "Q2") (pin "5") (pinfunction "5_5") (pintype "passive"))
      (node (ref "Q2") (pin "6") (pinfunction "6_6") (pintype "passive"))
      (node (ref "Q2") (pin "7") (pinfunction "7_7") (pintype "passive"))
      (node (ref "Q2") (pin "8") (pinfunction "8_8") (pintype "passive"))
    )
    (net (code "53") (name "Net-(Q3-Pad2)") (class "Default")
      (node (ref "Q3") (pin "2") (pintype "passive"))
      (node (ref "R89") (pin "2") (pinfunction "2_2") (pintype "passive"))
    )
    (net (code "54") (name "Net-(Q3-Pad4)") (class "Default")
      (node (ref "Q3") (pin "4") (pinfunction "4_4") (pintype "passive"))
      (node (ref "R90") (pin "2") (pinfunction "2_2") (pintype "passive"))
    )
    (net (code "55") (name "Net-(T1-Pad1)") (class "Default")
      (node (ref "T1") (pin "1") (pinfunction "1_1") (pintype "passive"))
      (node (ref "T1") (pin "5") (pinfunction "5_5") (pintype "passive"))
    )
    (net (code "56") (name "Net-(T1-Pad11)") (class "Default")
      (node (ref "T1") (pin "11") (pinfunction "11_11") (pintype "passive"))
      (node (ref "T1") (pin "7") (pinfunction "7_7") (pintype "passive"))
    )
    (net (code "57") (name "Net-(T1-Pad12)") (class "Default")
      (node (ref "T1") (pin "12") (pinfunction "12_12") (pintype "passive"))
      (node (ref "T1") (pin "8") (pinfunction "8_8") (pintype "passive"))
    )
    (net (code "58") (name "Net-(U4-CLN)") (class "Default")
      (node (ref "C7") (pin "2") (pinfunction "2_2") (pintype "passive"))
      (node (ref "R13") (pin "2") (pinfunction "2_2") (pintype "passive"))
      (node (ref "U4") (pin "2") (pinfunction "CLN_2") (pintype "input"))
    )
    (net (code "59") (name "Net-(U4-CSN)") (class "Default")
      (node (ref "R25") (pin "1") (pinfunction "1_1") (pintype "passive"))
      (node (ref "U4") (pin "27") (pinfunction "CSN_27") (pintype "input"))
    )
    (net (code "60") (name "Net-(U4-CSP)") (class "Default")
      (node (ref "R19") (pin "1") (pinfunction "1_1") (pintype "passive"))
      (node (ref "U4") (pin "26") (pinfunction "CSP_26") (pintype "input"))
    )
    (net (code "61") (name "Net-(U4-ISENSE)") (class "Default")
      (node (ref "R16") (pin "1") (pinfunction "1_1") (pintype "passive"))
      (node (ref "U4") (pin "29") (pinfunction "ISENSE_29") (pintype "input"))
    )
    (net (code "62") (name "Net-(U4-THA)") (class "Default")
      (node (ref "R15") (pin "2") (pinfunction "2_2") (pintype "passive"))
      (node (ref "U4") (pin "20") (pinfunction "THA_20") (pintype "input"))
    )
    (net (code "63") (name "Net-(U4-THB)") (class "Default")
      (node (ref "R17") (pin "2") (pinfunction "2_2") (pintype "passive"))
      (node (ref "U4") (pin "21") (pinfunction "THB_21") (pintype "input"))
    )
    (net (code "64") (name "unconnected-(T1-Pad3)") (class "Default")
      (node (ref "T1") (pin "3") (pinfunction "3_3") (pintype "passive+no_connect"))
    )
    (net (code "65") (name "unconnected-(T1-Pad6)") (class "Default")
      (node (ref "T1") (pin "6") (pinfunction "6_6") (pintype "passive+no_connect"))
    )
    (net (code "66") (name "unconnected-(U4-NC-Pad36)") (class "Default")
      (node (ref "U4") (pin "36") (pinfunction "NC_36") (pintype "passive+no_connect"))
    )
  )
)
